# Project_04_Schematic.net
KiCad netlist of a schematic drawn in EAGLE
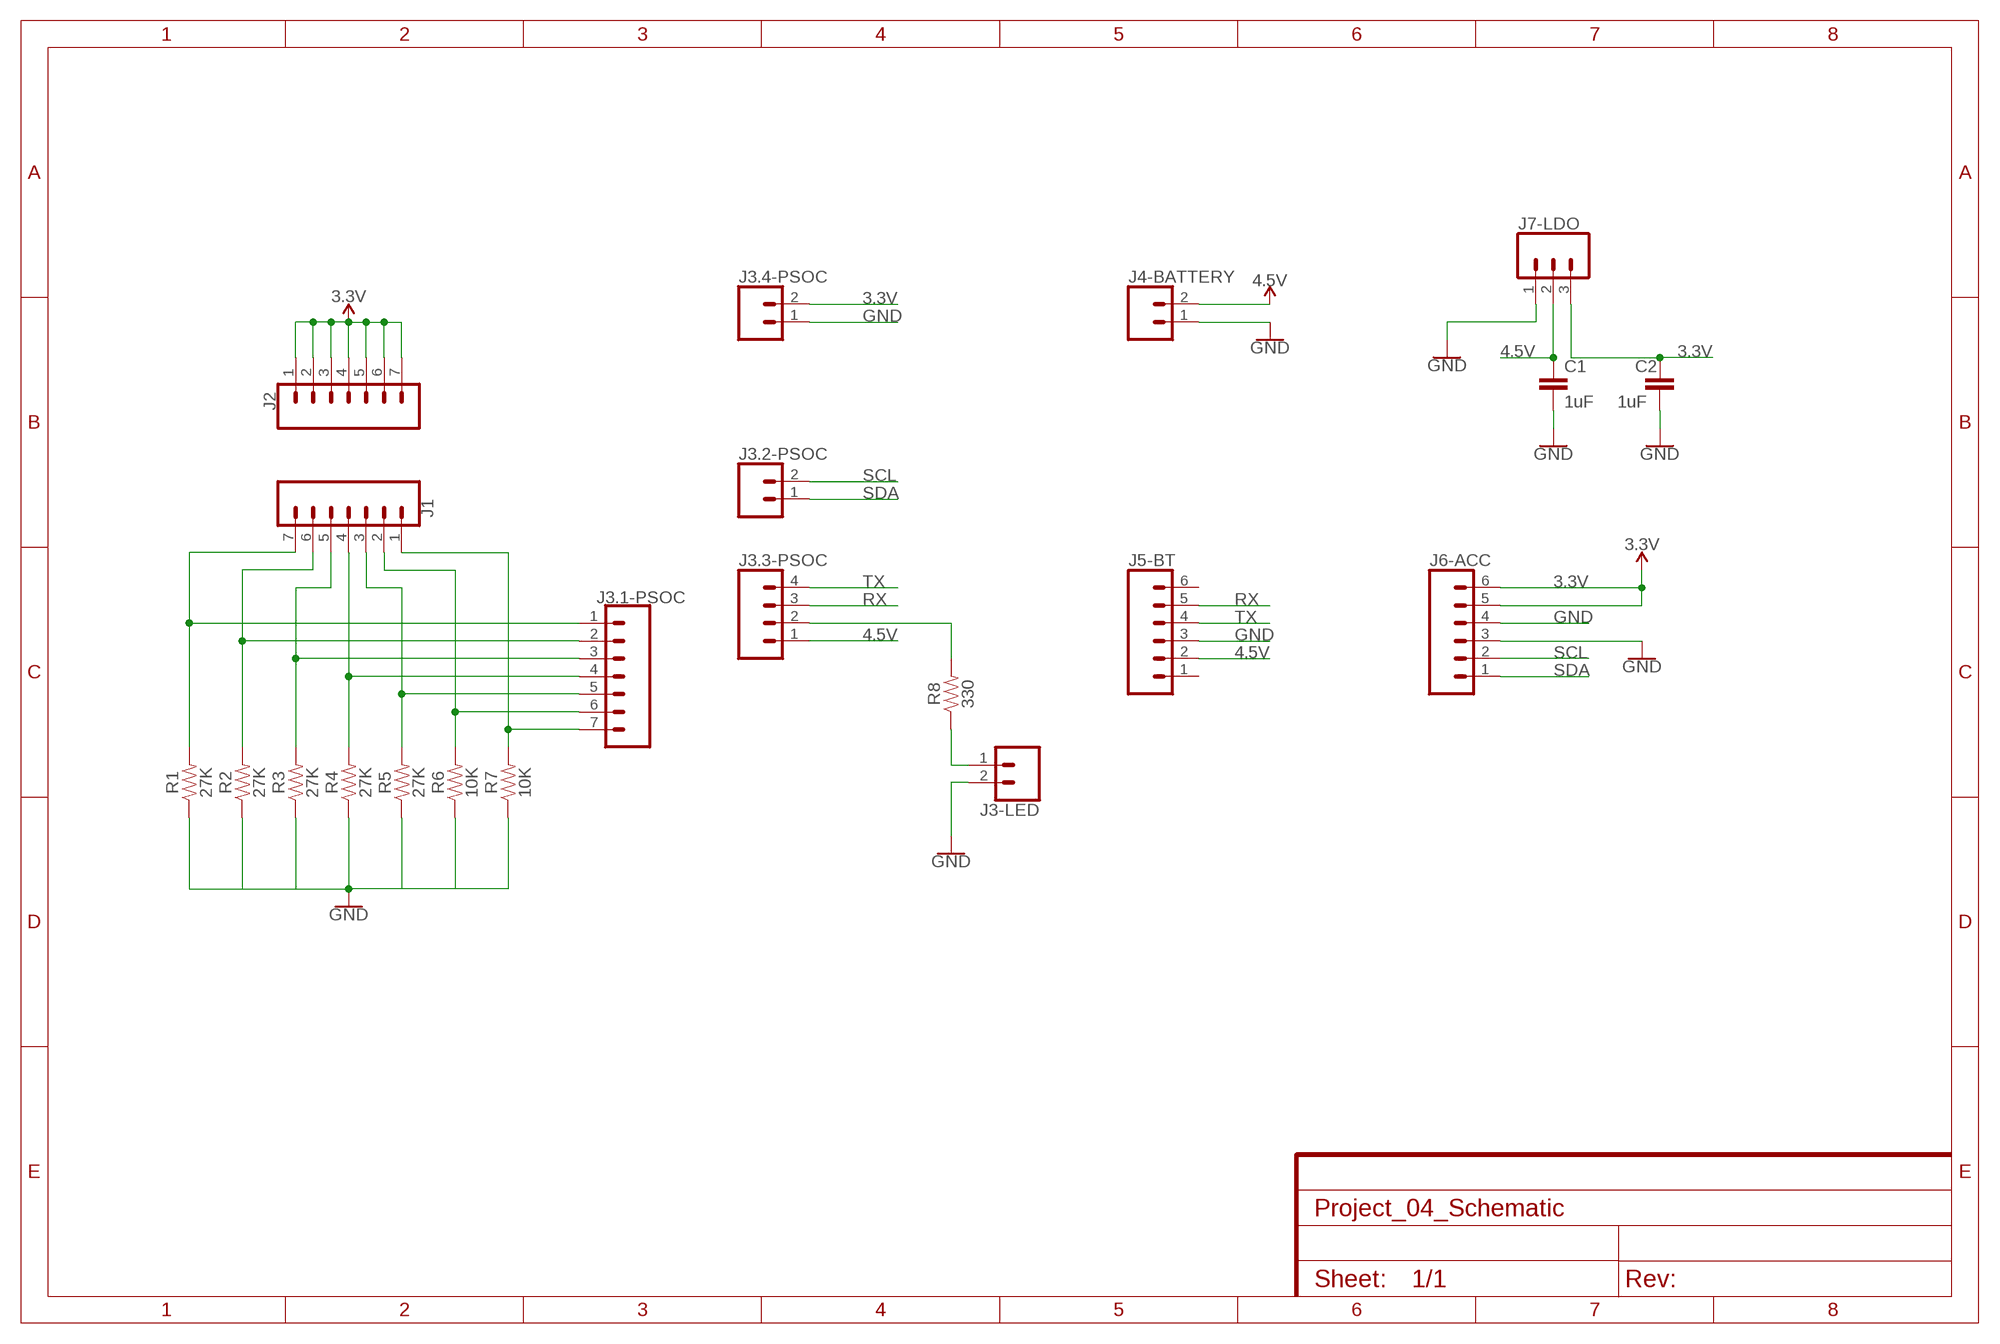
[diagram p0: schematic, sheet 1]

(export (version "E")
  (design (tool "Eeschema 10.0.6"))
  (components
    (comp (ref "C1")
      (value "1uF")
      (footprint "eagle-import:CAP-PTH-2.54")
      (libsource (lib "eagle-import") (part "22PF-PTH-2.54MM-200V-5%"))
    )
    (comp (ref "C2")
      (value "1uF")
      (footprint "eagle-import:CAP-PTH-2.54")
      (libsource (lib "eagle-import") (part "22PF-PTH-2.54MM-200V-5%"))
    )
    (comp (ref "J1")
      (value "CONN_07")
      (footprint "eagle-import:1X07")
      (libsource (lib "eagle-import") (part "CONN_07"))
    )
    (comp (ref "J2")
      (value "CONN_07")
      (footprint "eagle-import:1X07")
      (libsource (lib "eagle-import") (part "CONN_07"))
    )
    (comp (ref "J3-LED")
      (value "CONN_02")
      (footprint "eagle-import:1X02")
      (libsource (lib "eagle-import") (part "CONN_02"))
    )
    (comp (ref "J3.1-PSOC")
      (value "CONN_07")
      (footprint "eagle-import:1X07")
      (libsource (lib "eagle-import") (part "CONN_07"))
    )
    (comp (ref "J3.2-PSOC")
      (value "CONN_02")
      (footprint "eagle-import:1X02")
      (libsource (lib "eagle-import") (part "CONN_02"))
    )
    (comp (ref "J3.3-PSOC")
      (value "CONN_04PTH")
      (footprint "eagle-import:1X04")
      (libsource (lib "eagle-import") (part "CONN_04PTH"))
    )
    (comp (ref "J3.4-PSOC")
      (value "CONN_02")
      (footprint "eagle-import:1X02")
      (libsource (lib "eagle-import") (part "CONN_02"))
    )
    (comp (ref "J4-BATTERY")
      (value "CONN_02")
      (footprint "eagle-import:1X02")
      (libsource (lib "eagle-import") (part "CONN_02"))
    )
    (comp (ref "J5-BT")
      (value "CONN_06SILK_FEMALE_PTH")
      (footprint "eagle-import:1X06")
      (libsource (lib "eagle-import") (part "CONN_06SILK_FEMALE_PTH"))
    )
    (comp (ref "J6-ACC")
      (value "CONN_06SILK_FEMALE_PTH")
      (footprint "eagle-import:1X06")
      (libsource (lib "eagle-import") (part "CONN_06SILK_FEMALE_PTH"))
    )
    (comp (ref "J7-LDO")
      (value "CONN_03")
      (footprint "eagle-import:1X03")
      (libsource (lib "eagle-import") (part "CONN_03"))
    )
    (comp (ref "R1")
      (value "27K")
      (footprint "eagle-import:AXIAL-0.3")
      (libsource (lib "eagle-import") (part "RESISTORAXIAL-0.3"))
    )
    (comp (ref "R2")
      (value "27K")
      (footprint "eagle-import:AXIAL-0.3")
      (libsource (lib "eagle-import") (part "RESISTORAXIAL-0.3"))
    )
    (comp (ref "R3")
      (value "27K")
      (footprint "eagle-import:AXIAL-0.3")
      (libsource (lib "eagle-import") (part "RESISTORAXIAL-0.3"))
    )
    (comp (ref "R4")
      (value "27K")
      (footprint "eagle-import:AXIAL-0.3")
      (libsource (lib "eagle-import") (part "RESISTORAXIAL-0.3"))
    )
    (comp (ref "R5")
      (value "27K")
      (footprint "eagle-import:AXIAL-0.3")
      (libsource (lib "eagle-import") (part "RESISTORAXIAL-0.3"))
    )
    (comp (ref "R6")
      (value "10K")
      (footprint "eagle-import:AXIAL-0.3")
      (libsource (lib "eagle-import") (part "RESISTORAXIAL-0.3"))
    )
    (comp (ref "R7")
      (value "10K")
      (footprint "eagle-import:AXIAL-0.3")
      (libsource (lib "eagle-import") (part "RESISTORAXIAL-0.3"))
    )
    (comp (ref "R8")
      (value "330")
      (footprint "eagle-import:AXIAL-0.3")
      (libsource (lib "eagle-import") (part "RESISTORAXIAL-0.3"))
    )
  )
  (nets
    (net (code "1") (name "/RX") (class "Default")
      (node (ref "J3.3-PSOC") (pin "3") (pinfunction "3_3") (pintype "passive"))
      (node (ref "J5-BT") (pin "5") (pinfunction "5_5") (pintype "passive"))
    )
    (net (code "2") (name "/SCL") (class "Default")
      (node (ref "J3.2-PSOC") (pin "2") (pinfunction "2_2") (pintype "passive"))
      (node (ref "J6-ACC") (pin "2") (pinfunction "2_2") (pintype "passive"))
    )
    (net (code "3") (name "/SDA") (class "Default")
      (node (ref "J3.2-PSOC") (pin "1") (pinfunction "1_1") (pintype "passive"))
      (node (ref "J6-ACC") (pin "1") (pinfunction "1_1") (pintype "passive"))
    )
    (net (code "4") (name "/TX") (class "Default")
      (node (ref "J3.3-PSOC") (pin "4") (pinfunction "4_4") (pintype "passive"))
      (node (ref "J5-BT") (pin "4") (pinfunction "4_4") (pintype "passive"))
    )
    (net (code "5") (name "3.3V") (class "Default")
      (node (ref "C2") (pin "1") (pinfunction "1_1") (pintype "passive"))
      (node (ref "J2") (pin "1") (pinfunction "1_1") (pintype "passive"))
      (node (ref "J2") (pin "2") (pinfunction "2_2") (pintype "passive"))
      (node (ref "J2") (pin "3") (pinfunction "3_3") (pintype "passive"))
      (node (ref "J2") (pin "4") (pinfunction "4_4") (pintype "passive"))
      (node (ref "J2") (pin "5") (pinfunction "5_5") (pintype "passive"))
      (node (ref "J2") (pin "6") (pinfunction "6_6") (pintype "passive"))
      (node (ref "J2") (pin "7") (pinfunction "7_7") (pintype "passive"))
      (node (ref "J3.4-PSOC") (pin "2") (pinfunction "2_2") (pintype "passive"))
      (node (ref "J6-ACC") (pin "5") (pinfunction "5_5") (pintype "passive"))
      (node (ref "J6-ACC") (pin "6") (pinfunction "6_6") (pintype "passive"))
      (node (ref "J7-LDO") (pin "3") (pinfunction "3_3") (pintype "passive"))
    )
    (net (code "6") (name "3.7V") (class "Default")
      (node (ref "C1") (pin "1") (pinfunction "1_1") (pintype "passive"))
      (node (ref "J3.3-PSOC") (pin "1") (pinfunction "1_1") (pintype "passive"))
      (node (ref "J4-BATTERY") (pin "2") (pinfunction "2_2") (pintype "passive"))
      (node (ref "J5-BT") (pin "2") (pinfunction "2_2") (pintype "passive"))
      (node (ref "J7-LDO") (pin "2") (pinfunction "2_2") (pintype "passive"))
    )
    (net (code "7") (name "GND") (class "Default")
      (node (ref "C1") (pin "2") (pinfunction "2_2") (pintype "passive"))
      (node (ref "C2") (pin "2") (pinfunction "2_2") (pintype "passive"))
      (node (ref "J3-LED") (pin "2") (pinfunction "2_2") (pintype "passive"))
      (node (ref "J3.4-PSOC") (pin "1") (pinfunction "1_1") (pintype "passive"))
      (node (ref "J4-BATTERY") (pin "1") (pinfunction "1_1") (pintype "passive"))
      (node (ref "J5-BT") (pin "3") (pinfunction "3_3") (pintype "passive"))
      (node (ref "J6-ACC") (pin "3") (pinfunction "3_3") (pintype "passive"))
      (node (ref "J6-ACC") (pin "4") (pinfunction "4_4") (pintype "passive"))
      (node (ref "J7-LDO") (pin "1") (pinfunction "1_1") (pintype "passive"))
      (node (ref "R1") (pin "P$1") (pinfunction "1_P$1") (pintype "passive"))
      (node (ref "R2") (pin "P$1") (pinfunction "1_P$1") (pintype "passive"))
      (node (ref "R3") (pin "P$1") (pinfunction "1_P$1") (pintype "passive"))
      (node (ref "R4") (pin "P$1") (pinfunction "1_P$1") (pintype "passive"))
      (node (ref "R5") (pin "P$1") (pinfunction "1_P$1") (pintype "passive"))
      (node (ref "R6") (pin "P$1") (pinfunction "1_P$1") (pintype "passive"))
      (node (ref "R7") (pin "P$1") (pinfunction "1_P$1") (pintype "passive"))
    )
    (net (code "8") (name "Net-(R1-2)") (class "Default")
      (node (ref "J1") (pin "7") (pinfunction "7_7") (pintype "passive"))
      (node (ref "J3.1-PSOC") (pin "1") (pinfunction "1_1") (pintype "passive"))
      (node (ref "R1") (pin "P$2") (pinfunction "2_P$2") (pintype "passive"))
    )
    (net (code "9") (name "Net-(R2-2)") (class "Default")
      (node (ref "J1") (pin "6") (pinfunction "6_6") (pintype "passive"))
      (node (ref "J3.1-PSOC") (pin "2") (pinfunction "2_2") (pintype "passive"))
      (node (ref "R2") (pin "P$2") (pinfunction "2_P$2") (pintype "passive"))
    )
    (net (code "10") (name "Net-(R3-2)") (class "Default")
      (node (ref "J1") (pin "5") (pinfunction "5_5") (pintype "passive"))
      (node (ref "J3.1-PSOC") (pin "3") (pinfunction "3_3") (pintype "passive"))
      (node (ref "R3") (pin "P$2") (pinfunction "2_P$2") (pintype "passive"))
    )
    (net (code "11") (name "Net-(R4-2)") (class "Default")
      (node (ref "J1") (pin "4") (pinfunction "4_4") (pintype "passive"))
      (node (ref "J3.1-PSOC") (pin "4") (pinfunction "4_4") (pintype "passive"))
      (node (ref "R4") (pin "P$2") (pinfunction "2_P$2") (pintype "passive"))
    )
    (net (code "12") (name "Net-(R5-2)") (class "Default")
      (node (ref "J1") (pin "3") (pinfunction "3_3") (pintype "passive"))
      (node (ref "J3.1-PSOC") (pin "5") (pinfunction "5_5") (pintype "passive"))
      (node (ref "R5") (pin "P$2") (pinfunction "2_P$2") (pintype "passive"))
    )
    (net (code "13") (name "Net-(R6-2)") (class "Default")
      (node (ref "J1") (pin "2") (pinfunction "2_2") (pintype "passive"))
      (node (ref "J3.1-PSOC") (pin "6") (pinfunction "6_6") (pintype "passive"))
      (node (ref "R6") (pin "P$2") (pinfunction "2_P$2") (pintype "passive"))
    )
    (net (code "14") (name "Net-(R7-2)") (class "Default")
      (node (ref "J1") (pin "1") (pinfunction "1_1") (pintype "passive"))
      (node (ref "J3.1-PSOC") (pin "7") (pinfunction "7_7") (pintype "passive"))
      (node (ref "R7") (pin "P$2") (pinfunction "2_P$2") (pintype "passive"))
    )
    (net (code "15") (name "Net-(R8-1)") (class "Default")
      (node (ref "J3-LED") (pin "1") (pinfunction "1_1") (pintype "passive"))
      (node (ref "R8") (pin "P$1") (pinfunction "1_P$1") (pintype "passive"))
    )
    (net (code "16") (name "Net-(R8-2)") (class "Default")
      (node (ref "J3.3-PSOC") (pin "2") (pinfunction "2_2") (pintype "passive"))
      (node (ref "R8") (pin "P$2") (pinfunction "2_P$2") (pintype "passive"))
    )
    (net (code "17") (name "unconnected-(J5-BT-Pad1)") (class "Default")
      (node (ref "J5-BT") (pin "1") (pinfunction "1_1") (pintype "passive"))
    )
    (net (code "18") (name "unconnected-(J5-BT-Pad6)") (class "Default")
      (node (ref "J5-BT") (pin "6") (pinfunction "6_6") (pintype "passive"))
    )
  )
)
